# air-sense.net
KiCad netlist of a schematic drawn in EAGLE
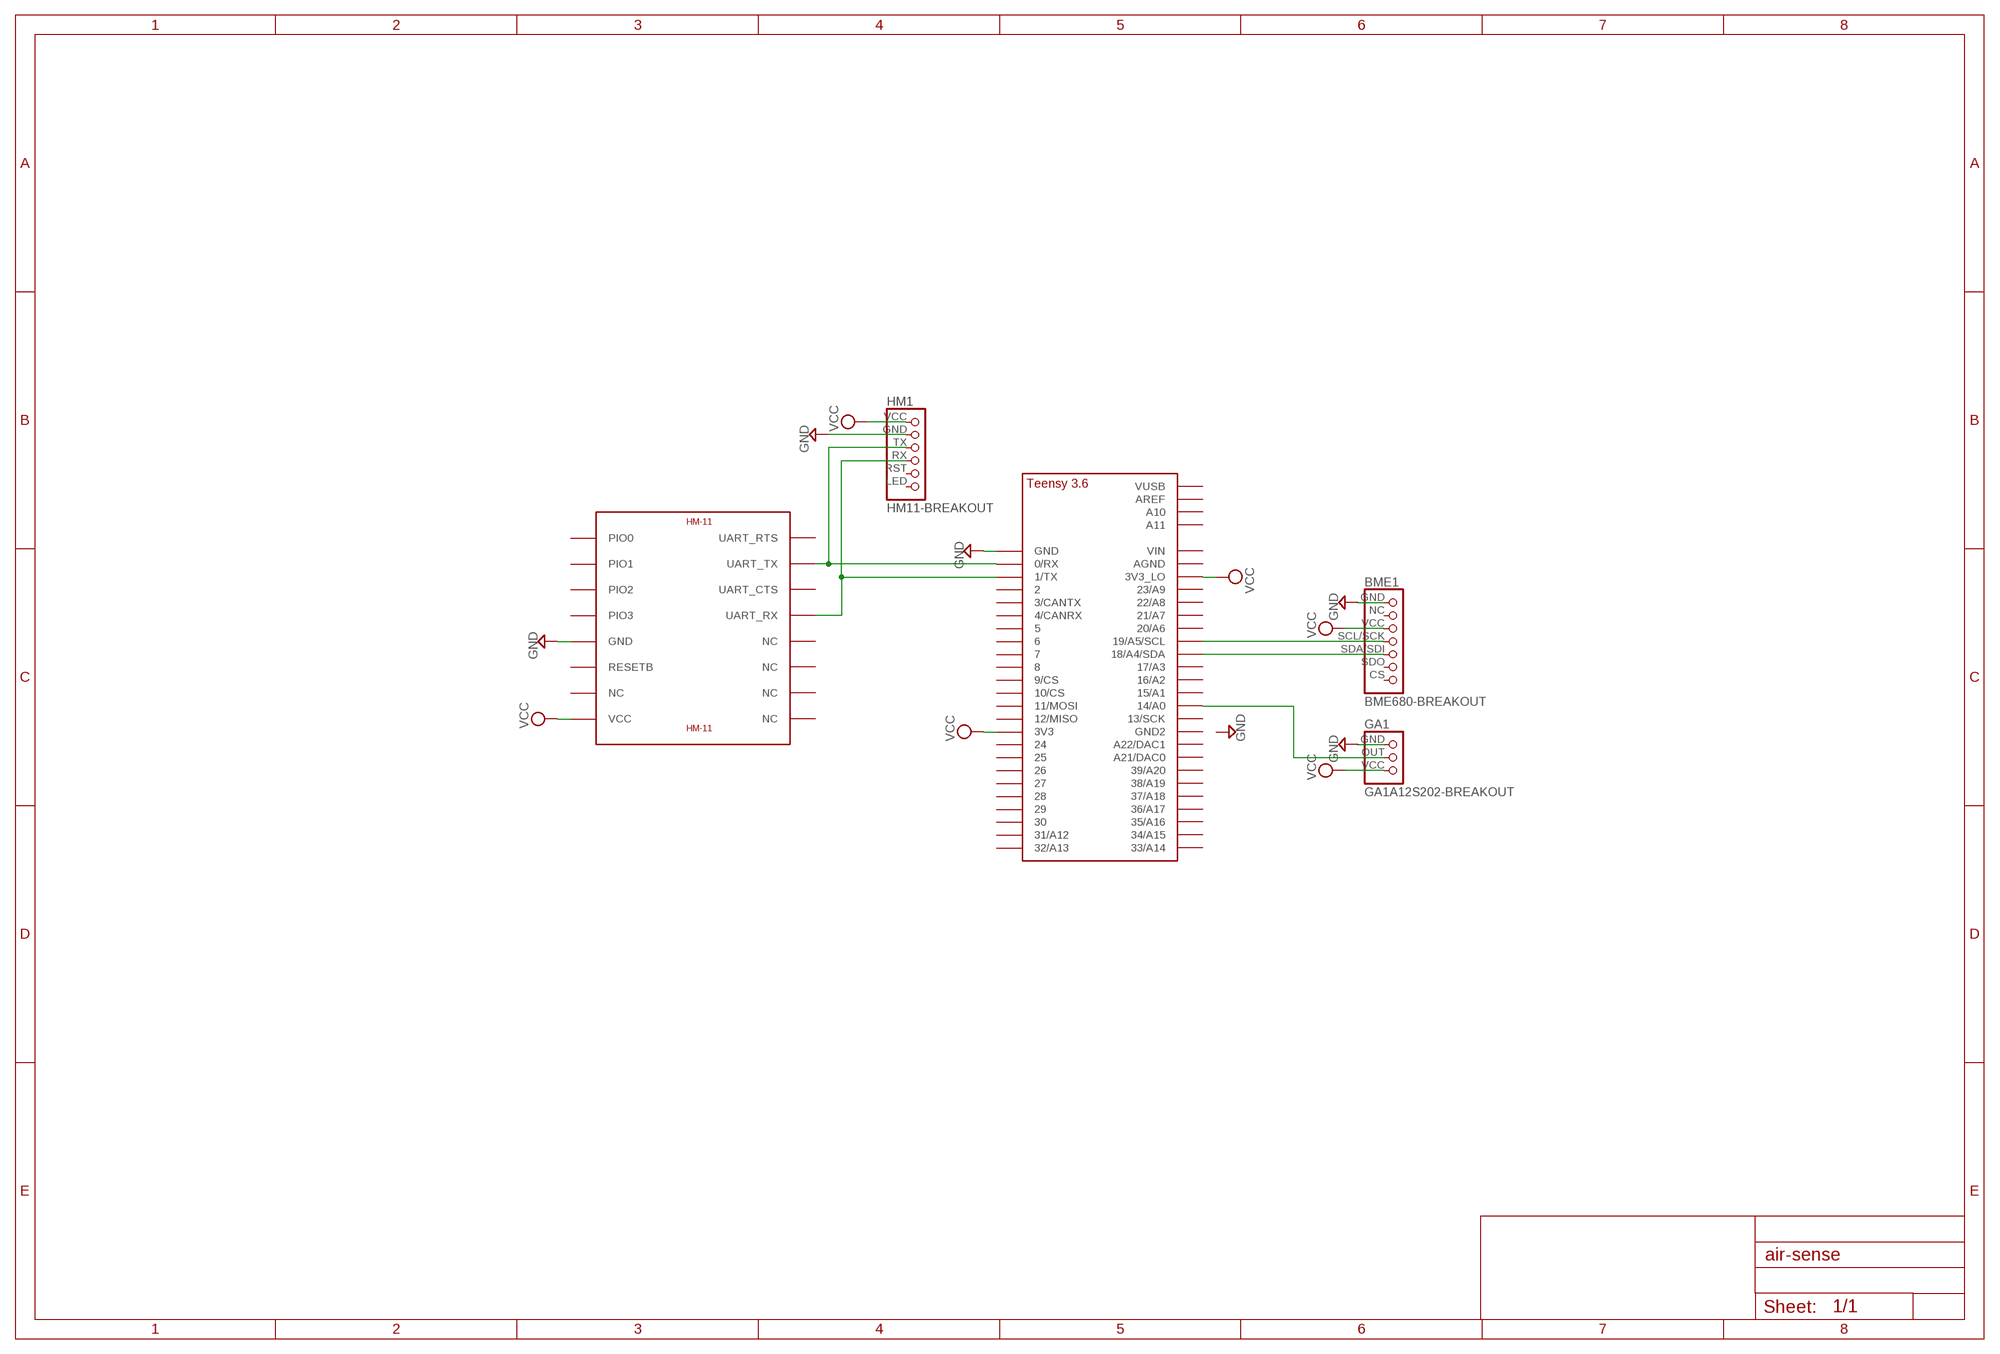
[diagram p0: schematic, sheet 1]

(export (version "E")
  (design (tool "Eeschema 10.0.6"))
  (components
    (comp (ref "BME1")
      (value "BME680-BREAKOUT")
      (footprint "eagle-import:BME680-1X07")
      (libsource (lib "eagle-import") (part "BME680-BREAKOUT"))
    )
    (comp (ref "GA1")
      (value "GA1A12S202-BREAKOUT")
      (footprint "eagle-import:GA1A12S202-BREAKOUT")
      (libsource (lib "eagle-import") (part "GA1A12S202-BREAKOUT"))
    )
    (comp (ref "HM1")
      (value "HM11-BREAKOUT")
      (footprint "eagle-import:HM11-BREAKOUT")
      (libsource (lib "eagle-import") (part "HM11-BREAKOUT"))
    )
    (comp (ref "U$1")
      (value "TEENSY_3.5/3.6_BASIC")
      (footprint "eagle-import:TEENSY_3.5_3.6_BASIC")
      (libsource (lib "eagle-import") (part "TEENSY_3.5/3.6_BASIC"))
    )
    (comp (ref "U$2")
      (value "HM-11")
      (footprint "eagle-import:HM-11")
      (libsource (lib "eagle-import") (part "HM-11"))
    )
  )
  (nets
    (net (code "1") (name "GND") (class "Default")
      (node (ref "BME1") (pin "GND") (pinfunction "GND_GND") (pintype "passive"))
      (node (ref "GA1") (pin "GND") (pinfunction "GND_GND") (pintype "passive"))
      (node (ref "HM1") (pin "GND") (pinfunction "GND_GND") (pintype "passive"))
      (node (ref "U$1") (pin "GND") (pinfunction "GND_GND") (pintype "bidirectional"))
      (node (ref "U$2") (pin "GND") (pinfunction "GND_GND") (pintype "bidirectional"))
    )
    (net (code "2") (name "Net-(BME1-PadSCL{slash}SCK)") (class "Default")
      (node (ref "BME1") (pin "SCL/SCK") (pinfunction "SCL/SCK_SCL/SCK") (pintype "passive"))
      (node (ref "U$1") (pin "19/A5/SCL") (pinfunction "19/A5/SCL_19/A5/SCL") (pintype "bidirectional"))
    )
    (net (code "3") (name "Net-(BME1-PadSDA{slash}SDI)") (class "Default")
      (node (ref "BME1") (pin "SDA/SDI") (pinfunction "SDA/SDI_SDA/SDI") (pintype "passive"))
      (node (ref "U$1") (pin "18/A4/SDA") (pinfunction "18/A4/SDA_18/A4/SDA") (pintype "bidirectional"))
    )
    (net (code "4") (name "Net-(GA1-PadOUT)") (class "Default")
      (node (ref "GA1") (pin "OUT") (pinfunction "OUT_OUT") (pintype "passive"))
      (node (ref "U$1") (pin "14/A0") (pinfunction "14/A0_14/A0") (pintype "bidirectional"))
    )
    (net (code "5") (name "Net-(HM1-PadRX)") (class "Default")
      (node (ref "HM1") (pin "RX") (pinfunction "RX_RX") (pintype "passive"))
      (node (ref "U$1") (pin "1/TX") (pinfunction "1/TX_1/TX") (pintype "bidirectional"))
      (node (ref "U$2") (pin "UART_RX") (pinfunction "UART_RX_UART_RX") (pintype "bidirectional"))
    )
    (net (code "6") (name "Net-(HM1-PadTX)") (class "Default")
      (node (ref "HM1") (pin "TX") (pinfunction "TX_TX") (pintype "passive"))
      (node (ref "U$1") (pin "0/RX") (pinfunction "0/RX_0/RX") (pintype "bidirectional"))
      (node (ref "U$2") (pin "UART_TX") (pinfunction "UART_TX_UART_TX") (pintype "bidirectional"))
    )
    (net (code "7") (name "VCC") (class "Default")
      (node (ref "BME1") (pin "VCC") (pinfunction "VCC_VCC") (pintype "passive"))
      (node (ref "GA1") (pin "VCC") (pinfunction "VCC_VCC") (pintype "passive"))
      (node (ref "HM1") (pin "VCC") (pinfunction "VCC_VCC") (pintype "passive"))
      (node (ref "U$1") (pin "3V3") (pinfunction "3V3_3V3") (pintype "bidirectional"))
      (node (ref "U$1") (pin "3V3_LO") (pinfunction "3V3_LO_3V3_LO") (pintype "bidirectional"))
      (node (ref "U$2") (pin "VCC") (pinfunction "VCC_VCC") (pintype "bidirectional"))
    )
    (net (code "8") (name "unconnected-(BME1-PadCS)") (class "Default")
      (node (ref "BME1") (pin "CS") (pinfunction "CS_CS") (pintype "passive"))
    )
    (net (code "9") (name "unconnected-(BME1-PadNC)") (class "Default")
      (node (ref "BME1") (pin "NC") (pinfunction "NC_NC") (pintype "passive"))
    )
    (net (code "10") (name "unconnected-(BME1-PadSDO)") (class "Default")
      (node (ref "BME1") (pin "SDO") (pinfunction "SDO_SDO") (pintype "passive"))
    )
    (net (code "11") (name "unconnected-(HM1-PadLED)") (class "Default")
      (node (ref "HM1") (pin "LED") (pinfunction "LED_LED") (pintype "passive"))
    )
    (net (code "12") (name "unconnected-(HM1-PadRST)") (class "Default")
      (node (ref "HM1") (pin "RST") (pinfunction "RST_RST") (pintype "passive"))
    )
    (net (code "13") (name "unconnected-(U$1-A21{slash}DAC0-Pad21{slash}DAC0)") (class "Default")
      (node (ref "U$1") (pin "21/DAC0") (pinfunction "A21/DAC0_21/DAC0") (pintype "bidirectional"))
    )
    (net (code "14") (name "unconnected-(U$1-Pad2)") (class "Default")
      (node (ref "U$1") (pin "2") (pinfunction "2_2") (pintype "bidirectional"))
    )
    (net (code "15") (name "unconnected-(U$1-Pad3{slash}CANTX)") (class "Default")
      (node (ref "U$1") (pin "3/CANTX") (pinfunction "3/CANTX_3/CANTX") (pintype "bidirectional"))
    )
    (net (code "16") (name "unconnected-(U$1-Pad4{slash}CANRX)") (class "Default")
      (node (ref "U$1") (pin "4/CANRX") (pinfunction "4/CANRX_4/CANRX") (pintype "bidirectional"))
    )
    (net (code "17") (name "unconnected-(U$1-Pad5)") (class "Default")
      (node (ref "U$1") (pin "5") (pinfunction "5_5") (pintype "bidirectional"))
    )
    (net (code "18") (name "unconnected-(U$1-Pad6)") (class "Default")
      (node (ref "U$1") (pin "6") (pinfunction "6_6") (pintype "bidirectional"))
    )
    (net (code "19") (name "unconnected-(U$1-Pad7)") (class "Default")
      (node (ref "U$1") (pin "7") (pinfunction "7_7") (pintype "bidirectional"))
    )
    (net (code "20") (name "unconnected-(U$1-Pad8)") (class "Default")
      (node (ref "U$1") (pin "8") (pinfunction "8_8") (pintype "bidirectional"))
    )
    (net (code "21") (name "unconnected-(U$1-Pad9{slash}CS)") (class "Default")
      (node (ref "U$1") (pin "9/CS") (pinfunction "9/CS_9/CS") (pintype "bidirectional"))
    )
    (net (code "22") (name "unconnected-(U$1-Pad10{slash}CS)") (class "Default")
      (node (ref "U$1") (pin "10/CS") (pinfunction "10/CS_10/CS") (pintype "bidirectional"))
    )
    (net (code "23") (name "unconnected-(U$1-Pad11{slash}MOSI)") (class "Default")
      (node (ref "U$1") (pin "11/MOSI") (pinfunction "11/MOSI_11/MOSI") (pintype "bidirectional"))
    )
    (net (code "24") (name "unconnected-(U$1-Pad12{slash}MISO)") (class "Default")
      (node (ref "U$1") (pin "12/MISO") (pinfunction "12/MISO_12/MISO") (pintype "bidirectional"))
    )
    (net (code "25") (name "unconnected-(U$1-Pad13{slash}SCK)") (class "Default")
      (node (ref "U$1") (pin "13/SCK") (pinfunction "13/SCK_13/SCK") (pintype "bidirectional"))
    )
    (net (code "26") (name "unconnected-(U$1-Pad15{slash}A1)") (class "Default")
      (node (ref "U$1") (pin "15/A1") (pinfunction "15/A1_15/A1") (pintype "bidirectional"))
    )
    (net (code "27") (name "unconnected-(U$1-Pad16{slash}A2)") (class "Default")
      (node (ref "U$1") (pin "16/A2") (pinfunction "16/A2_16/A2") (pintype "bidirectional"))
    )
    (net (code "28") (name "unconnected-(U$1-Pad17{slash}A3)") (class "Default")
      (node (ref "U$1") (pin "17/A3") (pinfunction "17/A3_17/A3") (pintype "bidirectional"))
    )
    (net (code "29") (name "unconnected-(U$1-Pad20{slash}A6)") (class "Default")
      (node (ref "U$1") (pin "20/A6") (pinfunction "20/A6_20/A6") (pintype "bidirectional"))
    )
    (net (code "30") (name "unconnected-(U$1-Pad21{slash}A7)") (class "Default")
      (node (ref "U$1") (pin "21/A7") (pinfunction "21/A7_21/A7") (pintype "bidirectional"))
    )
    (net (code "31") (name "unconnected-(U$1-Pad22{slash}A8)") (class "Default")
      (node (ref "U$1") (pin "22/A8") (pinfunction "22/A8_22/A8") (pintype "bidirectional"))
    )
    (net (code "32") (name "unconnected-(U$1-Pad23{slash}A9)") (class "Default")
      (node (ref "U$1") (pin "23/A9") (pinfunction "23/A9_23/A9") (pintype "bidirectional"))
    )
    (net (code "33") (name "unconnected-(U$1-Pad24)") (class "Default")
      (node (ref "U$1") (pin "24") (pinfunction "24_24") (pintype "bidirectional"))
    )
    (net (code "34") (name "unconnected-(U$1-Pad25)") (class "Default")
      (node (ref "U$1") (pin "25") (pinfunction "25_25") (pintype "bidirectional"))
    )
    (net (code "35") (name "unconnected-(U$1-Pad26)") (class "Default")
      (node (ref "U$1") (pin "26") (pinfunction "26_26") (pintype "bidirectional"))
    )
    (net (code "36") (name "unconnected-(U$1-Pad27)") (class "Default")
      (node (ref "U$1") (pin "27") (pinfunction "27_27") (pintype "bidirectional"))
    )
    (net (code "37") (name "unconnected-(U$1-Pad28)") (class "Default")
      (node (ref "U$1") (pin "28") (pinfunction "28_28") (pintype "bidirectional"))
    )
    (net (code "38") (name "unconnected-(U$1-Pad29)") (class "Default")
      (node (ref "U$1") (pin "29") (pinfunction "29_29") (pintype "bidirectional"))
    )
    (net (code "39") (name "unconnected-(U$1-Pad30)") (class "Default")
      (node (ref "U$1") (pin "30") (pinfunction "30_30") (pintype "bidirectional"))
    )
    (net (code "40") (name "unconnected-(U$1-Pad31{slash}A12)") (class "Default")
      (node (ref "U$1") (pin "31/A12") (pinfunction "31/A12_31/A12") (pintype "bidirectional"))
    )
    (net (code "41") (name "unconnected-(U$1-Pad32{slash}A13)") (class "Default")
      (node (ref "U$1") (pin "32/A13") (pinfunction "32/A13_32/A13") (pintype "bidirectional"))
    )
    (net (code "42") (name "unconnected-(U$1-Pad33{slash}A14)") (class "Default")
      (node (ref "U$1") (pin "33/A14") (pinfunction "33/A14_33/A14") (pintype "bidirectional"))
    )
    (net (code "43") (name "unconnected-(U$1-Pad34{slash}A15)") (class "Default")
      (node (ref "U$1") (pin "34/A15") (pinfunction "34/A15_34/A15") (pintype "bidirectional"))
    )
    (net (code "44") (name "unconnected-(U$1-Pad35{slash}A16)") (class "Default")
      (node (ref "U$1") (pin "35/A16") (pinfunction "35/A16_35/A16") (pintype "bidirectional"))
    )
    (net (code "45") (name "unconnected-(U$1-Pad36{slash}A17)") (class "Default")
      (node (ref "U$1") (pin "36/A17") (pinfunction "36/A17_36/A17") (pintype "bidirectional"))
    )
    (net (code "46") (name "unconnected-(U$1-Pad37{slash}A18)") (class "Default")
      (node (ref "U$1") (pin "37/A18") (pinfunction "37/A18_37/A18") (pintype "bidirectional"))
    )
    (net (code "47") (name "unconnected-(U$1-Pad38{slash}A19)") (class "Default")
      (node (ref "U$1") (pin "38/A19") (pinfunction "38/A19_38/A19") (pintype "bidirectional"))
    )
    (net (code "48") (name "unconnected-(U$1-Pad39{slash}A20)") (class "Default")
      (node (ref "U$1") (pin "39/A20") (pinfunction "39/A20_39/A20") (pintype "bidirectional"))
    )
    (net (code "49") (name "unconnected-(U$1-PadA10)") (class "Default")
      (node (ref "U$1") (pin "A10") (pinfunction "A10_A10") (pintype "bidirectional"))
    )
    (net (code "50") (name "unconnected-(U$1-PadA11)") (class "Default")
      (node (ref "U$1") (pin "A11") (pinfunction "A11_A11") (pintype "bidirectional"))
    )
    (net (code "51") (name "unconnected-(U$1-PadA22{slash}DAC1)") (class "Default")
      (node (ref "U$1") (pin "A22/DAC1") (pinfunction "A22/DAC1_A22/DAC1") (pintype "bidirectional"))
    )
    (net (code "52") (name "unconnected-(U$1-PadAGND)") (class "Default")
      (node (ref "U$1") (pin "AGND") (pinfunction "AGND_AGND") (pintype "bidirectional"))
    )
    (net (code "53") (name "unconnected-(U$1-PadAREF)") (class "Default")
      (node (ref "U$1") (pin "AREF") (pinfunction "AREF_AREF") (pintype "bidirectional"))
    )
    (net (code "54") (name "unconnected-(U$1-PadGND2)") (class "Default")
      (node (ref "U$1") (pin "GND2") (pinfunction "GND2_GND2") (pintype "bidirectional"))
    )
    (net (code "55") (name "unconnected-(U$1-PadVIN)") (class "Default")
      (node (ref "U$1") (pin "VIN") (pinfunction "VIN_VIN") (pintype "bidirectional"))
    )
    (net (code "56") (name "unconnected-(U$1-PadVUSB)") (class "Default")
      (node (ref "U$1") (pin "VUSB") (pinfunction "VUSB_VUSB") (pintype "bidirectional"))
    )
    (net (code "57") (name "unconnected-(U$2-NC-PadNC@5)") (class "Default")
      (node (ref "U$2") (pin "NC@5") (pinfunction "NC_NC@5") (pintype "bidirectional"))
    )
    (net (code "58") (name "unconnected-(U$2-NC-PadNC@6)") (class "Default")
      (node (ref "U$2") (pin "NC@6") (pinfunction "NC_NC@6") (pintype "bidirectional"))
    )
    (net (code "59") (name "unconnected-(U$2-NC-PadNC@7)") (class "Default")
      (node (ref "U$2") (pin "NC@7") (pinfunction "NC_NC@7") (pintype "bidirectional"))
    )
    (net (code "60") (name "unconnected-(U$2-NC-PadNC@8)") (class "Default")
      (node (ref "U$2") (pin "NC@8") (pinfunction "NC_NC@8") (pintype "bidirectional"))
    )
    (net (code "61") (name "unconnected-(U$2-NC-PadNC@10)") (class "Default")
      (node (ref "U$2") (pin "NC@10") (pinfunction "NC_NC@10") (pintype "bidirectional"))
    )
    (net (code "62") (name "unconnected-(U$2-PadPIO0)") (class "Default")
      (node (ref "U$2") (pin "PIO0") (pinfunction "PIO0_PIO0") (pintype "bidirectional"))
    )
    (net (code "63") (name "unconnected-(U$2-PadPIO1)") (class "Default")
      (node (ref "U$2") (pin "PIO1") (pinfunction "PIO1_PIO1") (pintype "bidirectional"))
    )
    (net (code "64") (name "unconnected-(U$2-PadPIO2)") (class "Default")
      (node (ref "U$2") (pin "PIO2") (pinfunction "PIO2_PIO2") (pintype "bidirectional"))
    )
    (net (code "65") (name "unconnected-(U$2-PadPIO3)") (class "Default")
      (node (ref "U$2") (pin "PIO3") (pinfunction "PIO3_PIO3") (pintype "bidirectional"))
    )
    (net (code "66") (name "unconnected-(U$2-PadRESETB)") (class "Default")
      (node (ref "U$2") (pin "RESETB") (pinfunction "RESETB_RESETB") (pintype "bidirectional"))
    )
    (net (code "67") (name "unconnected-(U$2-PadUART_CTS)") (class "Default")
      (node (ref "U$2") (pin "UART_CTS") (pinfunction "UART_CTS_UART_CTS") (pintype "bidirectional"))
    )
    (net (code "68") (name "unconnected-(U$2-PadUART_RTS)") (class "Default")
      (node (ref "U$2") (pin "UART_RTS") (pinfunction "UART_RTS_UART_RTS") (pintype "bidirectional"))
    )
  )
)
